# 1-Schematic_BlinkingLightBoard2.net
KiCad netlist of a schematic drawn in EasyEDA
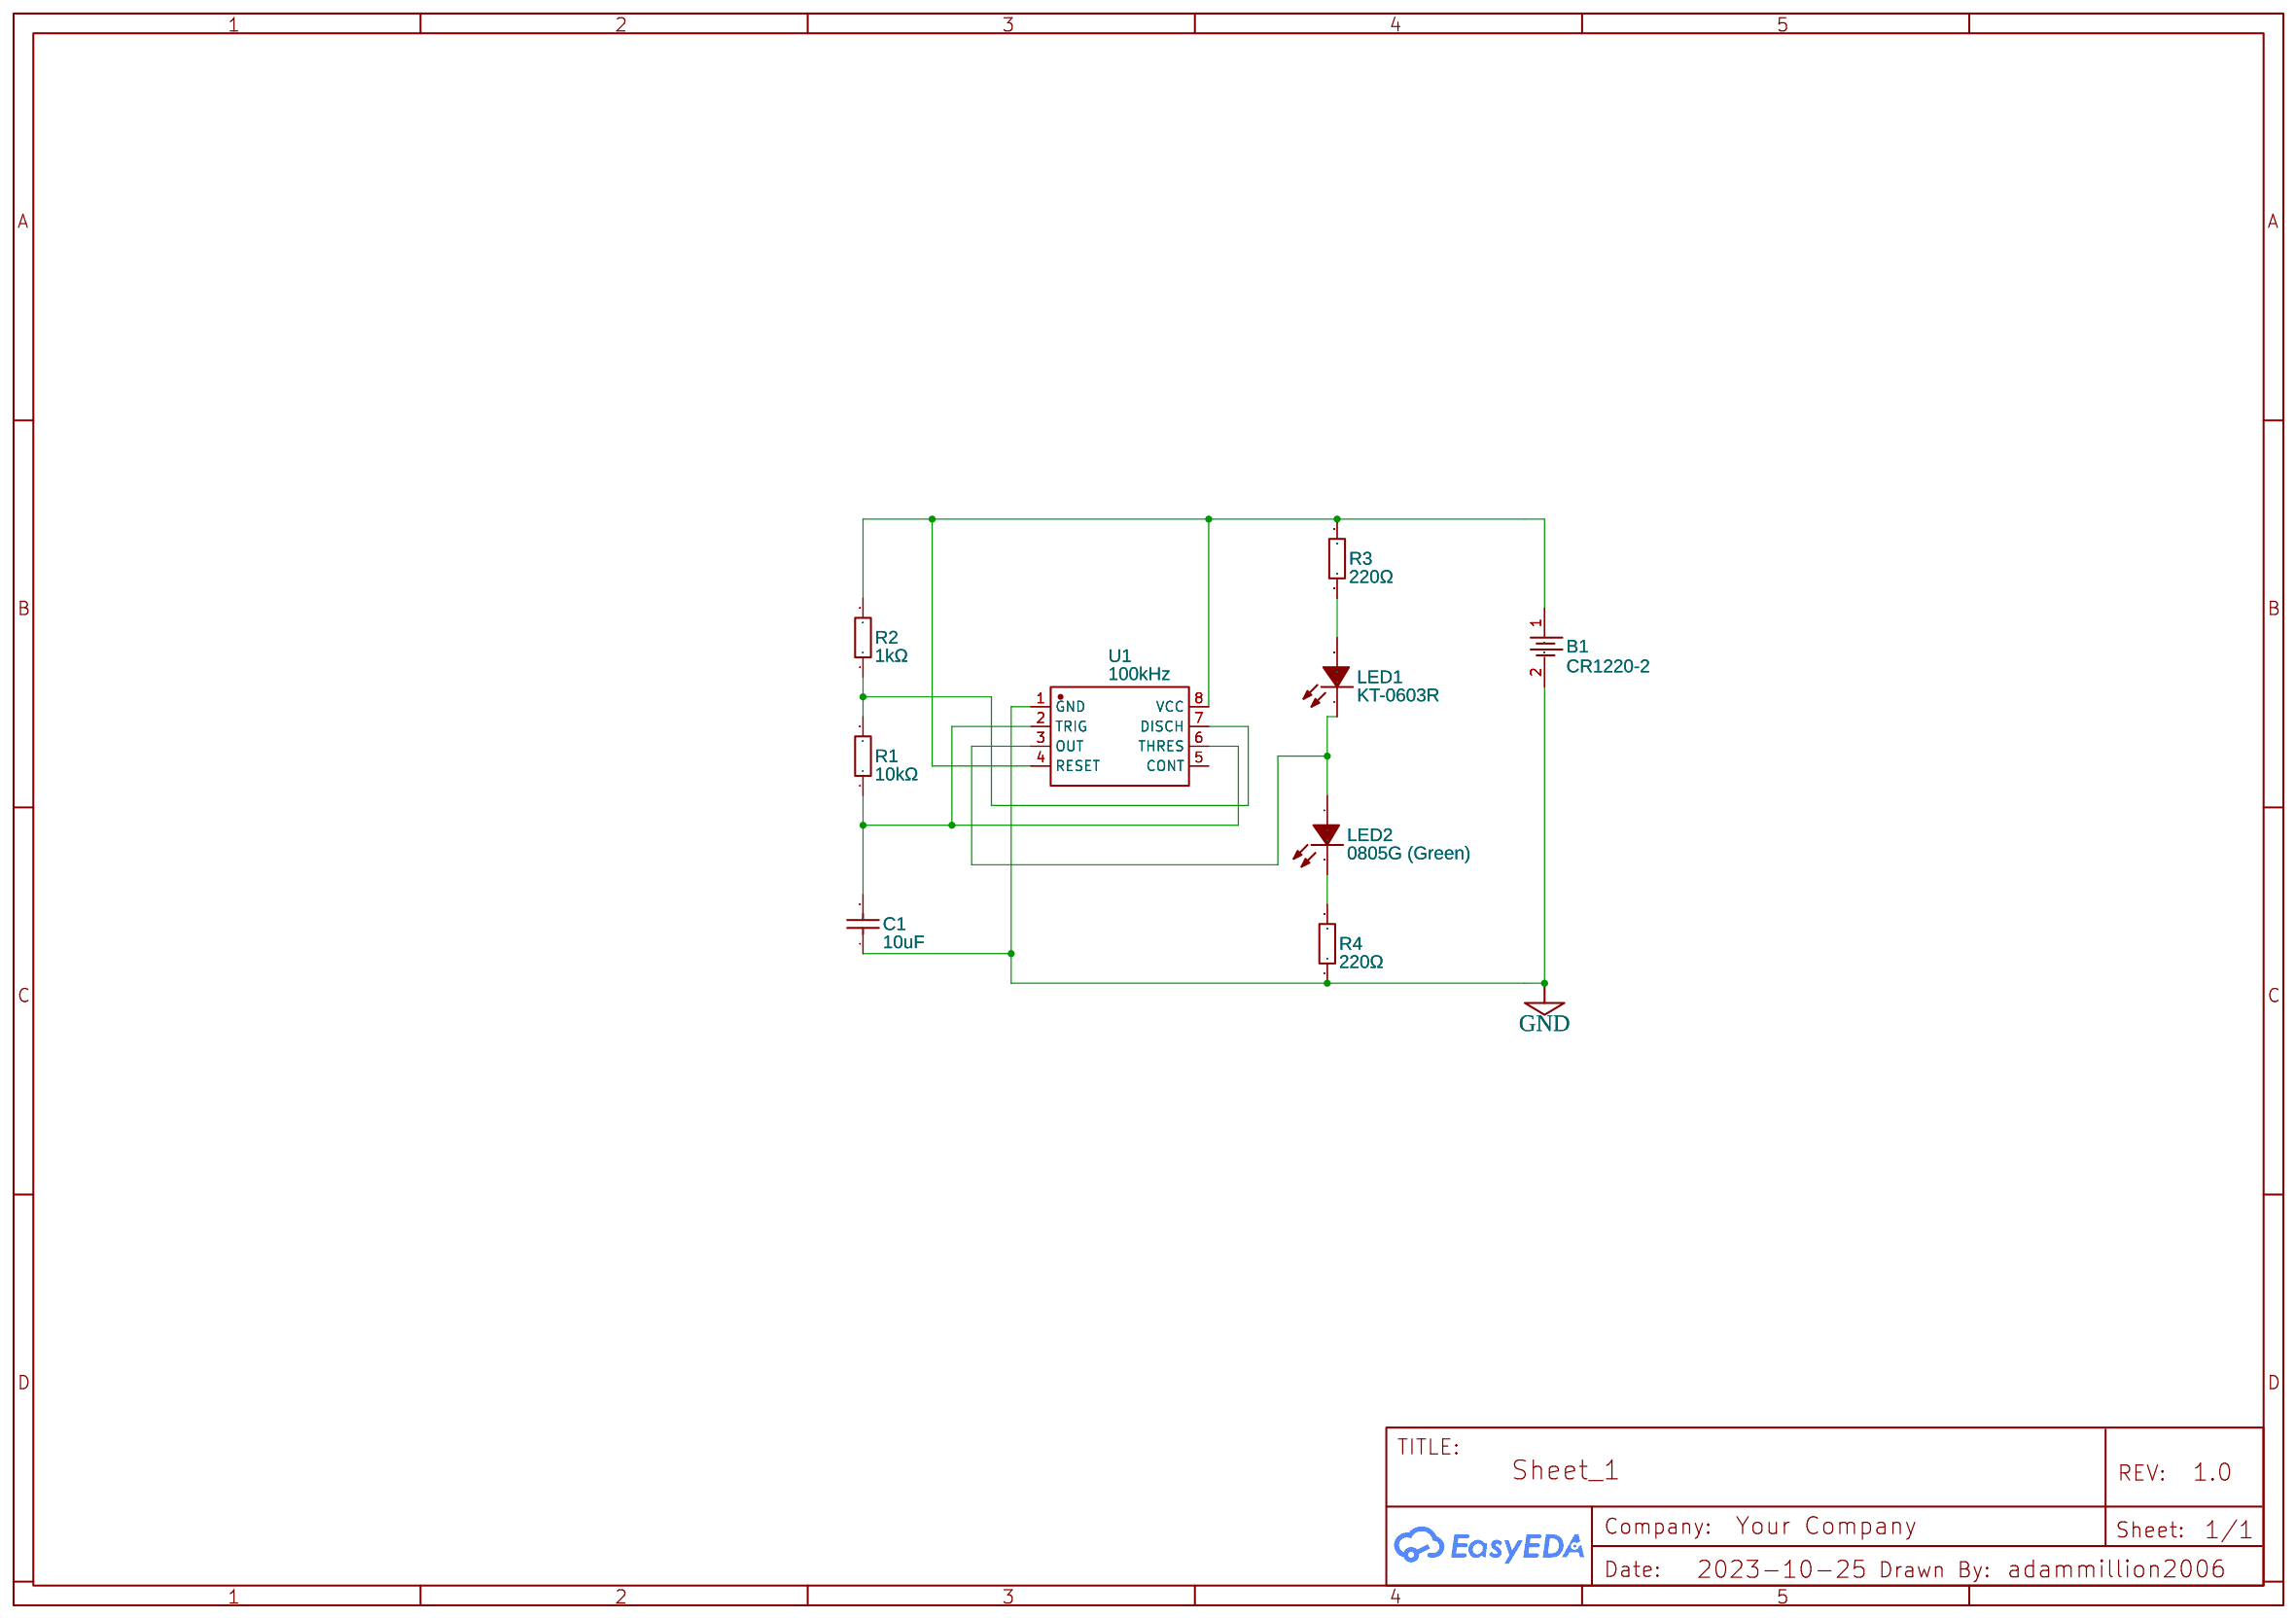
[diagram p0: schematic sheet]

(export (version "E")
  (design (tool "Eeschema 10.0.6"))
  (components
    (comp (ref "B1")
      (value "CR1220-2")
      (fields (field (name "Manufacturer") "Q&J"))
      (libsource (lib "") (part "CR1220-2"))
    )
    (comp (ref "C1")
      (value "10uF")
      (fields
        (field (name "Manufacturer Part") "CL05A106MQ5NUNC")
        (field (name "Manufacturer") "SAMSUNG(三星)")
      )
      (libsource (lib "") (part "CL05A106MQ5NUNC"))
    )
    (comp (ref "LED1")
      (value "KT-0603R")
      (fields (field (name "Manufacturer") "KENTO"))
      (libsource (lib "") (part "KT-0603R"))
    )
    (comp (ref "LED2")
      (value "0805G (Green)")
      (fields (field (name "Manufacturer Part") "KT-0805翠绿") (field (name "Manufacturer") "KENTO"))
      (libsource (lib "") (part "0805G (Green)"))
    )
    (comp (ref "R1")
      (value "10kΩ")
      (fields
        (field (name "Manufacturer Part") "0402WGF1002TCE")
        (field (name "Manufacturer") "UNI-ROYAL(厚声)")
      )
      (libsource (lib "") (part "0402WGF1002TCE"))
    )
    (comp (ref "R2")
      (value "1kΩ")
      (fields
        (field (name "Manufacturer Part") "0402WGF1001TCE")
        (field (name "Manufacturer") "UNI-ROYAL(厚声)")
      )
      (libsource (lib "") (part "0402WGF1001TCE"))
    )
    (comp (ref "R3")
      (value "220Ω")
      (fields
        (field (name "Manufacturer Part") "0603WAF2200T5E")
        (field (name "Manufacturer") "UNI-ROYAL(厚声)")
      )
      (libsource (lib "") (part "0603WAF2200T5E"))
    )
    (comp (ref "R4")
      (value "220Ω")
      (fields
        (field (name "Manufacturer Part") "0603WAF2200T5E")
        (field (name "Manufacturer") "UNI-ROYAL(厚声)")
      )
      (libsource (lib "") (part "0603WAF2200T5E"))
    )
    (comp (ref "U1")
      (value "100kHz")
      (fields (field (name "Manufacturer Part") "NE555P") (field (name "Manufacturer") "TI(德州仪器)"))
      (libsource (lib "") (part "NE555P"))
    )
  )
  (nets
    (net (code "1") (name "GND") (class "Default")
      (node (ref "B1") (pin "2") (pinfunction "2_2") (pintype "input"))
      (node (ref "C1") (pin "1") (pinfunction "1_1") (pintype "input"))
      (node (ref "R4") (pin "1") (pinfunction "1_1") (pintype "input"))
      (node (ref "U1") (pin "1") (pinfunction "GND_1") (pintype "unspecified"))
    )
    (net (code "2") (name "Net-(LED1-A)") (class "Default")
      (node (ref "LED1") (pin "2") (pinfunction "A_2") (pintype "unspecified"))
      (node (ref "R3") (pin "1") (pinfunction "1_1") (pintype "input"))
    )
    (net (code "3") (name "Net-(LED1-K)") (class "Default")
      (node (ref "LED1") (pin "1") (pinfunction "K_1") (pintype "unspecified"))
      (node (ref "LED2") (pin "1") (pinfunction "A_1") (pintype "unspecified"))
      (node (ref "U1") (pin "3") (pinfunction "OUT_3") (pintype "unspecified"))
    )
    (net (code "4") (name "Net-(LED2-K)") (class "Default")
      (node (ref "LED2") (pin "2") (pinfunction "K_2") (pintype "unspecified"))
      (node (ref "R4") (pin "2") (pinfunction "2_2") (pintype "input"))
    )
    (net (code "5") (name "Net-(U1-DISCH)") (class "Default")
      (node (ref "R1") (pin "2") (pinfunction "2_2") (pintype "input"))
      (node (ref "R2") (pin "1") (pinfunction "1_1") (pintype "input"))
      (node (ref "U1") (pin "7") (pinfunction "DISCH_7") (pintype "unspecified"))
    )
    (net (code "6") (name "Net-(U1-RESET)") (class "Default")
      (node (ref "B1") (pin "1") (pinfunction "1_1") (pintype "input"))
      (node (ref "R2") (pin "2") (pinfunction "2_2") (pintype "input"))
      (node (ref "R3") (pin "2") (pinfunction "2_2") (pintype "input"))
      (node (ref "U1") (pin "4") (pinfunction "RESET_4") (pintype "unspecified"))
      (node (ref "U1") (pin "8") (pinfunction "VCC_8") (pintype "unspecified"))
    )
    (net (code "7") (name "Net-(U1-THRES)") (class "Default")
      (node (ref "C1") (pin "2") (pinfunction "2_2") (pintype "input"))
      (node (ref "R1") (pin "1") (pinfunction "1_1") (pintype "input"))
      (node (ref "U1") (pin "2") (pinfunction "TRIG_2") (pintype "unspecified"))
      (node (ref "U1") (pin "6") (pinfunction "THRES_6") (pintype "unspecified"))
    )
    (net (code "8") (name "unconnected-(U1-CONT-Pad5)") (class "Default")
      (node (ref "U1") (pin "5") (pinfunction "CONT_5") (pintype "unspecified"))
    )
  )
)
